# schema.net
KiCad netlist of a schematic drawn in EAGLE
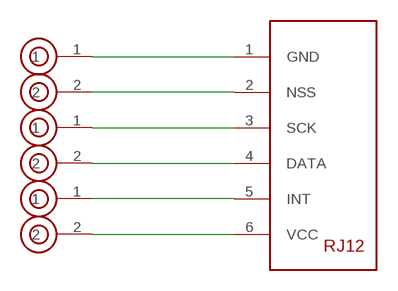
[diagram p0: schematic, sheet 1]

(export (version "E")
  (design (tool "Eeschema 10.0.6"))
  (components
    (comp (ref "U$1")
      (value "RJ12SMD")
      (footprint "eagle-import:RJ12_SMD")
      (libsource (lib "eagle-import") (part "RJ12SMD"))
    )
    (comp (ref "U$4")
      (value "GOLDPIN_2")
      (footprint "eagle-import:GOLDPIN_2_SMD")
      (libsource (lib "eagle-import") (part "GOLDPIN_2"))
    )
    (comp (ref "U$5")
      (value "GOLDPIN_2")
      (footprint "eagle-import:GOLDPIN_2_SMD")
      (libsource (lib "eagle-import") (part "GOLDPIN_2"))
    )
    (comp (ref "U$6")
      (value "GOLDPIN_2")
      (footprint "eagle-import:GOLDPIN_2_SMD")
      (libsource (lib "eagle-import") (part "GOLDPIN_2"))
    )
  )
  (nets
    (net (code "1") (name "Net-(U$1-DATA)") (class "Default")
      (node (ref "U$1") (pin "4") (pinfunction "DATA_4") (pintype "bidirectional"))
      (node (ref "U$5") (pin "2") (pinfunction "2_2") (pintype "bidirectional"))
    )
    (net (code "2") (name "Net-(U$1-GND)") (class "Default")
      (node (ref "U$1") (pin "1") (pinfunction "GND_1") (pintype "bidirectional"))
      (node (ref "U$6") (pin "1") (pinfunction "1_1") (pintype "bidirectional"))
    )
    (net (code "3") (name "Net-(U$1-INT)") (class "Default")
      (node (ref "U$1") (pin "5") (pinfunction "INT_5") (pintype "bidirectional"))
      (node (ref "U$4") (pin "1") (pinfunction "1_1") (pintype "bidirectional"))
    )
    (net (code "4") (name "Net-(U$1-NSS)") (class "Default")
      (node (ref "U$1") (pin "2") (pinfunction "NSS_2") (pintype "bidirectional"))
      (node (ref "U$6") (pin "2") (pinfunction "2_2") (pintype "bidirectional"))
    )
    (net (code "5") (name "Net-(U$1-SCK)") (class "Default")
      (node (ref "U$1") (pin "3") (pinfunction "SCK_3") (pintype "bidirectional"))
      (node (ref "U$5") (pin "1") (pinfunction "1_1") (pintype "bidirectional"))
    )
    (net (code "6") (name "Net-(U$1-VCC)") (class "Default")
      (node (ref "U$1") (pin "6") (pinfunction "VCC_6") (pintype "bidirectional"))
      (node (ref "U$4") (pin "2") (pinfunction "2_2") (pintype "bidirectional"))
    )
  )
)
